# camera-shield.net
KiCad netlist of a schematic drawn in EAGLE
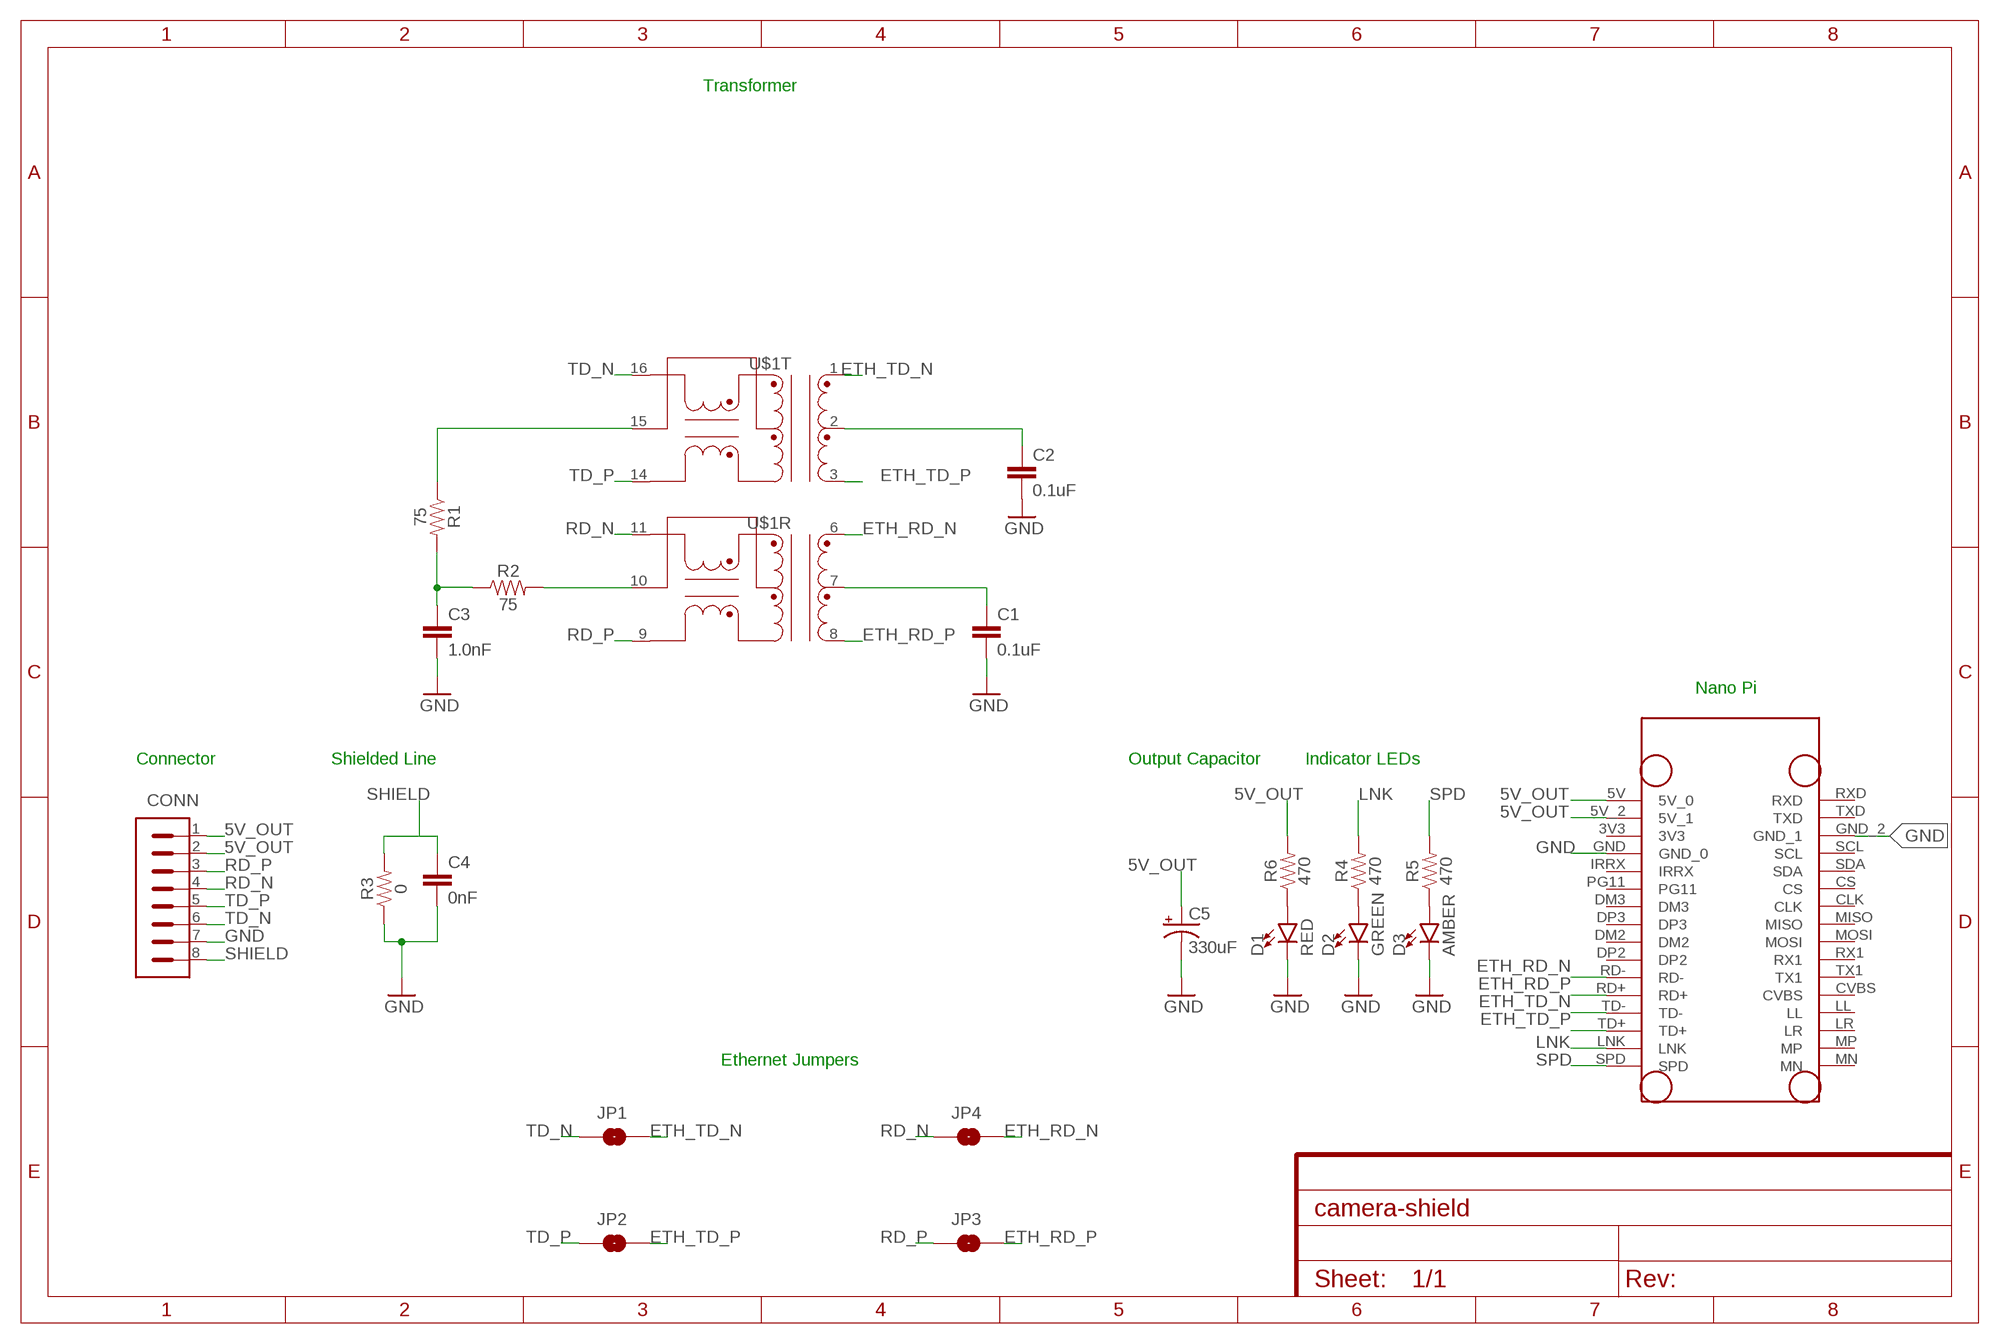
[diagram p0: schematic, sheet 1]

(export (version "E")
  (design (tool "Eeschema 10.0.6"))
  (components
    (comp (ref "C1")
      (value "0.1uF")
      (footprint "eagle-import:0603")
      (libsource (lib "eagle-import") (part "0.1UF-0603-25V-(+80/-20%)"))
    )
    (comp (ref "C2")
      (value "0.1uF")
      (footprint "eagle-import:0603")
      (libsource (lib "eagle-import") (part "0.1UF-0603-25V-(+80/-20%)"))
    )
    (comp (ref "C3")
      (value "1.0nF")
      (footprint "eagle-import:1206")
      (libsource (lib "eagle-import") (part "1.0UF-1206-50V-10%"))
    )
    (comp (ref "C4")
      (value "0nF")
      (footprint "eagle-import:0603")
      (libsource (lib "eagle-import") (part "3.3NF-0603-100V-10%"))
    )
    (comp (ref "C5")
      (value "337AXZ025M")
      (footprint "eagle-import:337AXZ025M")
      (libsource (lib "eagle-import") (part "337AXZ025M"))
    )
    (comp (ref "CONN")
      (value "PXC-8-RA-1778683")
      (footprint "eagle-import:PXC-8-RA-1778683")
      (libsource (lib "eagle-import") (part "PXC-8-RA-1778683"))
    )
    (comp (ref "D1")
      (value "RED")
      (footprint "eagle-import:FKIT-LED-1206")
      (libsource (lib "eagle-import") (part "LED-FKIT-1206"))
    )
    (comp (ref "D2")
      (value "GREEN")
      (footprint "eagle-import:FKIT-LED-1206")
      (libsource (lib "eagle-import") (part "LED-FKIT-1206"))
    )
    (comp (ref "D3")
      (value "AMBER")
      (footprint "eagle-import:FKIT-LED-1206")
      (libsource (lib "eagle-import") (part "LED-FKIT-1206"))
    )
    (comp (ref "JP1")
      (value "JUMPER-SMT_2_NO_NO-SILK")
      (footprint "eagle-import:SMT-JUMPER_2_NO_NO-SILK")
      (libsource (lib "eagle-import") (part "JUMPER-SMT_2_NO_NO-SILK"))
    )
    (comp (ref "JP2")
      (value "JUMPER-SMT_2_NO_NO-SILK")
      (footprint "eagle-import:SMT-JUMPER_2_NO_NO-SILK")
      (libsource (lib "eagle-import") (part "JUMPER-SMT_2_NO_NO-SILK"))
    )
    (comp (ref "JP3")
      (value "JUMPER-SMT_2_NO_NO-SILK")
      (footprint "eagle-import:SMT-JUMPER_2_NO_NO-SILK")
      (libsource (lib "eagle-import") (part "JUMPER-SMT_2_NO_NO-SILK"))
    )
    (comp (ref "JP4")
      (value "JUMPER-SMT_2_NO_NO-SILK")
      (footprint "eagle-import:SMT-JUMPER_2_NO_NO-SILK")
      (libsource (lib "eagle-import") (part "JUMPER-SMT_2_NO_NO-SILK"))
    )
    (comp (ref "R1")
      (value "75")
      (footprint "eagle-import:0603")
      (libsource (lib "eagle-import") (part "75KOHM-0603-1/10W-1%"))
    )
    (comp (ref "R2")
      (value "75")
      (footprint "eagle-import:0603")
      (libsource (lib "eagle-import") (part "75KOHM-0603-1/10W-1%"))
    )
    (comp (ref "R3")
      (value "0")
      (footprint "eagle-import:0603")
      (libsource (lib "eagle-import") (part "0OHM-0603-1/10W-5%"))
    )
    (comp (ref "R4")
      (value "470")
      (footprint "eagle-import:0603")
      (libsource (lib "eagle-import") (part "0OHM-0603-1/10W-5%"))
    )
    (comp (ref "R5")
      (value "470")
      (footprint "eagle-import:0603")
      (libsource (lib "eagle-import") (part "0OHM-0603-1/10W-5%"))
    )
    (comp (ref "R6")
      (value "470")
      (footprint "eagle-import:0603")
      (libsource (lib "eagle-import") (part "0OHM-0603-1/10W-5%"))
    )
    (comp (ref "U$1")
      (value "ETH-TRANS")
      (footprint "eagle-import:SOIC-16-WIDE")
      (libsource (lib "eagle-import") (part "ETH-TRANS"))
    )
    (comp (ref "U$2")
      (value "NANO_PI_CLEAN")
      (footprint "eagle-import:NANO_PI_CLEAN")
      (libsource (lib "eagle-import") (part "NANO_PI_CLEAN"))
    )
  )
  (nets
    (net (code "1") (name "/5V_OUT") (class "Default")
      (node (ref "C5") (pin "PLUS") (pinfunction "+_PLUS") (pintype "passive"))
      (node (ref "CONN") (pin "1") (pinfunction "1_1") (pintype "passive"))
      (node (ref "CONN") (pin "2") (pinfunction "2_2") (pintype "passive"))
      (node (ref "R6") (pin "2") (pinfunction "2_2") (pintype "passive"))
      (node (ref "U$2") (pin "5V") (pinfunction "5V_0_5V") (pintype "bidirectional"))
      (node (ref "U$2") (pin "5V_2") (pinfunction "5V_1_5V_2") (pintype "bidirectional"))
    )
    (net (code "2") (name "/ETH_RD_N") (class "Default")
      (node (ref "JP4") (pin "2") (pinfunction "2_2") (pintype "passive"))
      (node (ref "U$1") (pin "6") (pinfunction "D+_6") (pintype "passive"))
      (node (ref "U$2") (pin "RD-") (pinfunction "RD-_RD-") (pintype "bidirectional"))
    )
    (net (code "3") (name "/ETH_RD_P") (class "Default")
      (node (ref "JP3") (pin "2") (pinfunction "2_2") (pintype "passive"))
      (node (ref "U$1") (pin "8") (pinfunction "D-_8") (pintype "passive"))
      (node (ref "U$2") (pin "RD+") (pinfunction "RD+_RD+") (pintype "bidirectional"))
    )
    (net (code "4") (name "/ETH_TD_N") (class "Default")
      (node (ref "JP1") (pin "2") (pinfunction "2_2") (pintype "passive"))
      (node (ref "U$1") (pin "1") (pinfunction "D+_1") (pintype "passive"))
      (node (ref "U$2") (pin "TD-") (pinfunction "TD-_TD-") (pintype "bidirectional"))
    )
    (net (code "5") (name "/ETH_TD_P") (class "Default")
      (node (ref "JP2") (pin "2") (pinfunction "2_2") (pintype "passive"))
      (node (ref "U$1") (pin "3") (pinfunction "D-_3") (pintype "passive"))
      (node (ref "U$2") (pin "TD+") (pinfunction "TD+_TD+") (pintype "bidirectional"))
    )
    (net (code "6") (name "/LNK") (class "Default")
      (node (ref "R4") (pin "2") (pinfunction "2_2") (pintype "passive"))
      (node (ref "U$2") (pin "LNK") (pinfunction "LNK_LNK") (pintype "bidirectional"))
    )
    (net (code "7") (name "/RD_N") (class "Default")
      (node (ref "CONN") (pin "4") (pinfunction "4_4") (pintype "passive"))
      (node (ref "JP4") (pin "1") (pinfunction "1_1") (pintype "passive"))
      (node (ref "U$1") (pin "11") (pinfunction "X+_11") (pintype "passive"))
    )
    (net (code "8") (name "/RD_P") (class "Default")
      (node (ref "CONN") (pin "3") (pinfunction "3_3") (pintype "passive"))
      (node (ref "JP3") (pin "1") (pinfunction "1_1") (pintype "passive"))
      (node (ref "U$1") (pin "9") (pinfunction "X-_9") (pintype "passive"))
    )
    (net (code "9") (name "/SHIELD") (class "Default")
      (node (ref "C4") (pin "1") (pinfunction "1_1") (pintype "passive"))
      (node (ref "CONN") (pin "8") (pinfunction "8_8") (pintype "passive"))
      (node (ref "R3") (pin "2") (pinfunction "2_2") (pintype "passive"))
    )
    (net (code "10") (name "/SPD") (class "Default")
      (node (ref "R5") (pin "2") (pinfunction "2_2") (pintype "passive"))
      (node (ref "U$2") (pin "SPD") (pinfunction "SPD_SPD") (pintype "bidirectional"))
    )
    (net (code "11") (name "/TD_N") (class "Default")
      (node (ref "CONN") (pin "6") (pinfunction "6_6") (pintype "passive"))
      (node (ref "JP1") (pin "1") (pinfunction "1_1") (pintype "passive"))
      (node (ref "U$1") (pin "16") (pinfunction "X+_16") (pintype "passive"))
    )
    (net (code "12") (name "/TD_P") (class "Default")
      (node (ref "CONN") (pin "5") (pinfunction "5_5") (pintype "passive"))
      (node (ref "JP2") (pin "1") (pinfunction "1_1") (pintype "passive"))
      (node (ref "U$1") (pin "14") (pinfunction "X-_14") (pintype "passive"))
    )
    (net (code "13") (name "GND") (class "Default")
      (node (ref "C1") (pin "2") (pinfunction "2_2") (pintype "passive"))
      (node (ref "C2") (pin "2") (pinfunction "2_2") (pintype "passive"))
      (node (ref "C3") (pin "2") (pinfunction "2_2") (pintype "passive"))
      (node (ref "C4") (pin "2") (pinfunction "2_2") (pintype "passive"))
      (node (ref "C5") (pin "MINUS") (pinfunction "-_MINUS") (pintype "passive"))
      (node (ref "CONN") (pin "7") (pinfunction "7_7") (pintype "passive"))
      (node (ref "D1") (pin "C") (pinfunction "C_C") (pintype "passive"))
      (node (ref "D2") (pin "C") (pinfunction "C_C") (pintype "passive"))
      (node (ref "D3") (pin "C") (pinfunction "C_C") (pintype "passive"))
      (node (ref "R3") (pin "1") (pinfunction "1_1") (pintype "passive"))
      (node (ref "U$2") (pin "GND") (pinfunction "GND_0_GND") (pintype "bidirectional"))
      (node (ref "U$2") (pin "GND_2") (pinfunction "GND_1_GND_2") (pintype "bidirectional"))
    )
    (net (code "14") (name "Net-(C3-Pad1)") (class "Default")
      (node (ref "C3") (pin "1") (pinfunction "1_1") (pintype "passive"))
      (node (ref "R1") (pin "2") (pinfunction "2_2") (pintype "passive"))
      (node (ref "R2") (pin "1") (pinfunction "1_1") (pintype "passive"))
    )
    (net (code "15") (name "Net-(D1-PadA)") (class "Default")
      (node (ref "D1") (pin "A") (pinfunction "A_A") (pintype "passive"))
      (node (ref "R6") (pin "1") (pinfunction "1_1") (pintype "passive"))
    )
    (net (code "16") (name "Net-(D2-PadA)") (class "Default")
      (node (ref "D2") (pin "A") (pinfunction "A_A") (pintype "passive"))
      (node (ref "R4") (pin "1") (pinfunction "1_1") (pintype "passive"))
    )
    (net (code "17") (name "Net-(D3-PadA)") (class "Default")
      (node (ref "D3") (pin "A") (pinfunction "A_A") (pintype "passive"))
      (node (ref "R5") (pin "1") (pinfunction "1_1") (pintype "passive"))
    )
    (net (code "18") (name "Net-(U$1A-CT)") (class "Default")
      (node (ref "C1") (pin "1") (pinfunction "1_1") (pintype "passive"))
      (node (ref "U$1") (pin "7") (pinfunction "CT_7") (pintype "passive"))
    )
    (net (code "19") (name "Net-(U$1A-XCT)") (class "Default")
      (node (ref "R2") (pin "2") (pinfunction "2_2") (pintype "passive"))
      (node (ref "U$1") (pin "10") (pinfunction "XCT_10") (pintype "passive"))
    )
    (net (code "20") (name "Net-(U$1B-CT)") (class "Default")
      (node (ref "C2") (pin "1") (pinfunction "1_1") (pintype "passive"))
      (node (ref "U$1") (pin "2") (pinfunction "CT_2") (pintype "passive"))
    )
    (net (code "21") (name "Net-(U$1B-XCT)") (class "Default")
      (node (ref "R1") (pin "1") (pinfunction "1_1") (pintype "passive"))
      (node (ref "U$1") (pin "15") (pinfunction "XCT_15") (pintype "passive"))
    )
    (net (code "22") (name "unconnected-(U$2-Pad3V3)") (class "Default")
      (node (ref "U$2") (pin "3V3") (pinfunction "3V3_3V3") (pintype "bidirectional"))
    )
    (net (code "23") (name "unconnected-(U$2-PadCLK)") (class "Default")
      (node (ref "U$2") (pin "CLK") (pinfunction "CLK_CLK") (pintype "bidirectional"))
    )
    (net (code "24") (name "unconnected-(U$2-PadCS)") (class "Default")
      (node (ref "U$2") (pin "CS") (pinfunction "CS_CS") (pintype "bidirectional"))
    )
    (net (code "25") (name "unconnected-(U$2-PadCVBS)") (class "Default")
      (node (ref "U$2") (pin "CVBS") (pinfunction "CVBS_CVBS") (pintype "bidirectional"))
    )
    (net (code "26") (name "unconnected-(U$2-PadDM2)") (class "Default")
      (node (ref "U$2") (pin "DM2") (pinfunction "DM2_DM2") (pintype "bidirectional"))
    )
    (net (code "27") (name "unconnected-(U$2-PadDM3)") (class "Default")
      (node (ref "U$2") (pin "DM3") (pinfunction "DM3_DM3") (pintype "bidirectional"))
    )
    (net (code "28") (name "unconnected-(U$2-PadDP2)") (class "Default")
      (node (ref "U$2") (pin "DP2") (pinfunction "DP2_DP2") (pintype "bidirectional"))
    )
    (net (code "29") (name "unconnected-(U$2-PadDP3)") (class "Default")
      (node (ref "U$2") (pin "DP3") (pinfunction "DP3_DP3") (pintype "bidirectional"))
    )
    (net (code "30") (name "unconnected-(U$2-PadIRRX)") (class "Default")
      (node (ref "U$2") (pin "IRRX") (pinfunction "IRRX_IRRX") (pintype "bidirectional"))
    )
    (net (code "31") (name "unconnected-(U$2-PadLL)") (class "Default")
      (node (ref "U$2") (pin "LL") (pinfunction "LL_LL") (pintype "bidirectional"))
    )
    (net (code "32") (name "unconnected-(U$2-PadLR)") (class "Default")
      (node (ref "U$2") (pin "LR") (pinfunction "LR_LR") (pintype "bidirectional"))
    )
    (net (code "33") (name "unconnected-(U$2-PadMISO)") (class "Default")
      (node (ref "U$2") (pin "MISO") (pinfunction "MISO_MISO") (pintype "bidirectional"))
    )
    (net (code "34") (name "unconnected-(U$2-PadMN)") (class "Default")
      (node (ref "U$2") (pin "MN") (pinfunction "MN_MN") (pintype "bidirectional"))
    )
    (net (code "35") (name "unconnected-(U$2-PadMOSI)") (class "Default")
      (node (ref "U$2") (pin "MOSI") (pinfunction "MOSI_MOSI") (pintype "bidirectional"))
    )
    (net (code "36") (name "unconnected-(U$2-PadMP)") (class "Default")
      (node (ref "U$2") (pin "MP") (pinfunction "MP_MP") (pintype "bidirectional"))
    )
    (net (code "37") (name "unconnected-(U$2-PadPG11)") (class "Default")
      (node (ref "U$2") (pin "PG11") (pinfunction "PG11_PG11") (pintype "bidirectional"))
    )
    (net (code "38") (name "unconnected-(U$2-PadRX1)") (class "Default")
      (node (ref "U$2") (pin "RX1") (pinfunction "RX1_RX1") (pintype "bidirectional"))
    )
    (net (code "39") (name "unconnected-(U$2-PadRXD)") (class "Default")
      (node (ref "U$2") (pin "RXD") (pinfunction "RXD_RXD") (pintype "bidirectional"))
    )
    (net (code "40") (name "unconnected-(U$2-PadSCL)") (class "Default")
      (node (ref "U$2") (pin "SCL") (pinfunction "SCL_SCL") (pintype "bidirectional"))
    )
    (net (code "41") (name "unconnected-(U$2-PadSDA)") (class "Default")
      (node (ref "U$2") (pin "SDA") (pinfunction "SDA_SDA") (pintype "bidirectional"))
    )
    (net (code "42") (name "unconnected-(U$2-PadTX1)") (class "Default")
      (node (ref "U$2") (pin "TX1") (pinfunction "TX1_TX1") (pintype "bidirectional"))
    )
    (net (code "43") (name "unconnected-(U$2-PadTXD)") (class "Default")
      (node (ref "U$2") (pin "TXD") (pinfunction "TXD_TXD") (pintype "bidirectional"))
    )
  )
)
